# main.net
KiCad netlist of a schematic drawn in EAGLE
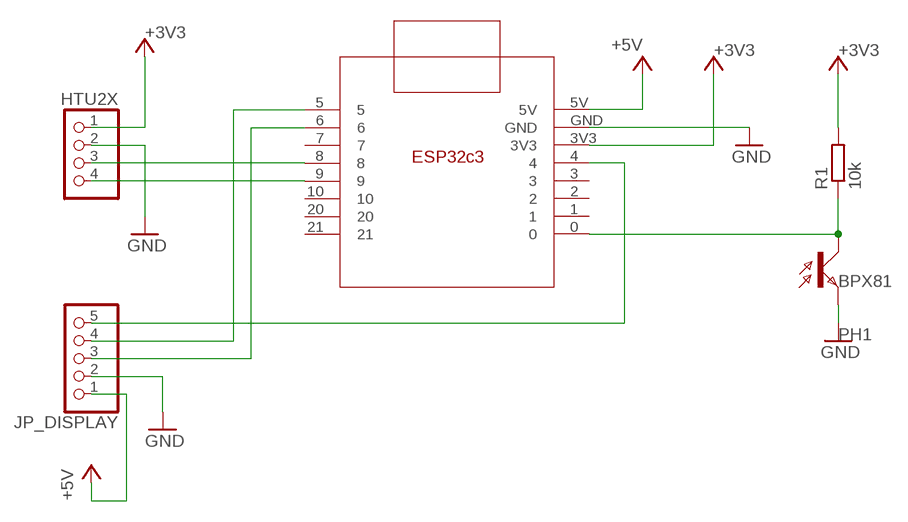
[diagram p0: schematic, sheet 1]

(export (version "E")
  (design (tool "Eeschema 10.0.6"))
  (components
    (comp (ref "HTU2X")
      (value "PINHD-1X4")
      (footprint "eagle-import:1X04")
      (libsource (lib "eagle-import") (part "PINHD-1X4"))
    )
    (comp (ref "JP_DISPLAY")
      (value "PINHD-1X5")
      (footprint "eagle-import:1X05")
      (libsource (lib "eagle-import") (part "PINHD-1X5"))
    )
    (comp (ref "PH1")
      (value "BPX81")
      (footprint "eagle-import:BPX81")
      (libsource (lib "eagle-import") (part "BPX81"))
    )
    (comp (ref "R1")
      (value "10k")
      (footprint "eagle-import:R0805")
      (libsource (lib "eagle-import") (part "R-EU_R0805"))
    )
    (comp (ref "U$2")
      (value "ESP32C3SMD")
      (footprint "eagle-import:ESP32C3_SMD")
      (libsource (lib "eagle-import") (part "ESP32C3SMD"))
    )
  )
  (nets
    (net (code "1") (name "+3V3") (class "Default")
      (node (ref "HTU2X") (pin "1") (pinfunction "1_1") (pintype "passive"))
      (node (ref "R1") (pin "2") (pinfunction "2_2") (pintype "passive"))
      (node (ref "U$2") (pin "3V3") (pinfunction "3V3_3V3") (pintype "bidirectional"))
    )
    (net (code "2") (name "+5V") (class "Default")
      (node (ref "JP_DISPLAY") (pin "1") (pinfunction "1_1") (pintype "passive"))
      (node (ref "U$2") (pin "5V") (pinfunction "5V_5V") (pintype "bidirectional"))
    )
    (net (code "3") (name "GND") (class "Default")
      (node (ref "HTU2X") (pin "2") (pinfunction "2_2") (pintype "passive"))
      (node (ref "JP_DISPLAY") (pin "2") (pinfunction "2_2") (pintype "passive"))
      (node (ref "PH1") (pin "E") (pinfunction "E_E") (pintype "passive"))
      (node (ref "U$2") (pin "GND") (pinfunction "GND_GND") (pintype "bidirectional"))
    )
    (net (code "4") (name "Net-(HTU2X-Pad3)") (class "Default")
      (node (ref "HTU2X") (pin "3") (pinfunction "3_3") (pintype "passive"))
      (node (ref "U$2") (pin "8") (pinfunction "8_8") (pintype "bidirectional"))
    )
    (net (code "5") (name "Net-(HTU2X-Pad4)") (class "Default")
      (node (ref "HTU2X") (pin "4") (pinfunction "4_4") (pintype "passive"))
      (node (ref "U$2") (pin "9") (pinfunction "9_9") (pintype "bidirectional"))
    )
    (net (code "6") (name "Net-(JP_DISPLAY-Pad3)") (class "Default")
      (node (ref "JP_DISPLAY") (pin "3") (pinfunction "3_3") (pintype "passive"))
      (node (ref "U$2") (pin "6") (pinfunction "6_6") (pintype "bidirectional"))
    )
    (net (code "7") (name "Net-(JP_DISPLAY-Pad4)") (class "Default")
      (node (ref "JP_DISPLAY") (pin "4") (pinfunction "4_4") (pintype "passive"))
      (node (ref "U$2") (pin "5") (pinfunction "5_5") (pintype "bidirectional"))
    )
    (net (code "8") (name "Net-(JP_DISPLAY-Pad5)") (class "Default")
      (node (ref "JP_DISPLAY") (pin "5") (pinfunction "5_5") (pintype "passive"))
      (node (ref "U$2") (pin "4") (pinfunction "4_4") (pintype "bidirectional"))
    )
    (net (code "9") (name "Net-(PH1-PadC)") (class "Default")
      (node (ref "PH1") (pin "C") (pinfunction "C_C") (pintype "passive"))
      (node (ref "R1") (pin "1") (pinfunction "1_1") (pintype "passive"))
      (node (ref "U$2") (pin "0") (pinfunction "0_0") (pintype "bidirectional"))
    )
    (net (code "10") (name "unconnected-(U$2-Pad1)") (class "Default")
      (node (ref "U$2") (pin "1") (pinfunction "1_1") (pintype "bidirectional"))
    )
    (net (code "11") (name "unconnected-(U$2-Pad2)") (class "Default")
      (node (ref "U$2") (pin "2") (pinfunction "2_2") (pintype "bidirectional"))
    )
    (net (code "12") (name "unconnected-(U$2-Pad3)") (class "Default")
      (node (ref "U$2") (pin "3") (pinfunction "3_3") (pintype "bidirectional"))
    )
    (net (code "13") (name "unconnected-(U$2-Pad7)") (class "Default")
      (node (ref "U$2") (pin "7") (pinfunction "7_7") (pintype "bidirectional"))
    )
    (net (code "14") (name "unconnected-(U$2-Pad10)") (class "Default")
      (node (ref "U$2") (pin "10") (pinfunction "10_10") (pintype "bidirectional"))
    )
    (net (code "15") (name "unconnected-(U$2-Pad20)") (class "Default")
      (node (ref "U$2") (pin "20") (pinfunction "20_20") (pintype "bidirectional"))
    )
    (net (code "16") (name "unconnected-(U$2-Pad21)") (class "Default")
      (node (ref "U$2") (pin "21") (pinfunction "21_21") (pintype "bidirectional"))
    )
  )
)
